# OUT_PIN.net
KiCad netlist of a schematic drawn in Altium Designer
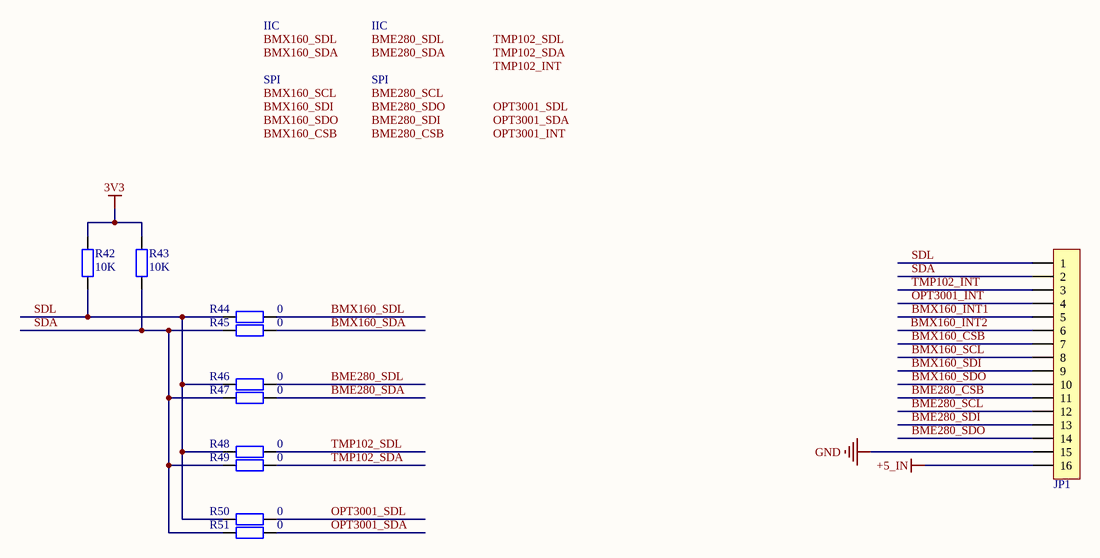
[diagram p0: OUT_PIN.SchDoc]

(export (version "E")
  (design (tool "Eeschema 10.0.6"))
  (components
    (comp (ref "JP1")
      (value "HDR-1X16")
      (footprint "HDR2.54-LI-16P")
      (description "16P接插件")
      (fields (field (name "版权归属") "源创客"))
      (libsource (lib "4.5   - 接插件-脚距2.54") (part "Header 16"))
    )
    (comp (ref "R42")
      (value "10K")
      (footprint "R 0402_L")
      (description "贴片电阻 0402 1%")
      (libsource (lib "3.1   - 电阻-电容-电感") (part "R"))
    )
    (comp (ref "R43")
      (value "10K")
      (footprint "R 0402_L")
      (description "贴片电阻 0402 1%")
      (libsource (lib "3.1   - 电阻-电容-电感") (part "R"))
    )
    (comp (ref "R44")
      (value "0")
      (footprint "R 0402_L")
      (description "贴片电阻")
      (libsource (lib "3.1   - 电阻-电容-电感") (part "R"))
    )
    (comp (ref "R45")
      (value "0")
      (footprint "R 0402_L")
      (description "贴片电阻")
      (libsource (lib "3.1   - 电阻-电容-电感") (part "R"))
    )
    (comp (ref "R46")
      (value "0")
      (footprint "R 0402_L")
      (description "贴片电阻")
      (libsource (lib "3.1   - 电阻-电容-电感") (part "R"))
    )
    (comp (ref "R47")
      (value "0")
      (footprint "R 0402_L")
      (description "贴片电阻")
      (libsource (lib "3.1   - 电阻-电容-电感") (part "R"))
    )
    (comp (ref "R48")
      (value "0")
      (footprint "R 0402_L")
      (description "贴片电阻")
      (libsource (lib "3.1   - 电阻-电容-电感") (part "R"))
    )
    (comp (ref "R49")
      (value "0")
      (footprint "R 0402_L")
      (description "贴片电阻")
      (libsource (lib "3.1   - 电阻-电容-电感") (part "R"))
    )
    (comp (ref "R50")
      (value "0")
      (footprint "R 0402_L")
      (description "贴片电阻")
      (libsource (lib "3.1   - 电阻-电容-电感") (part "R"))
    )
    (comp (ref "R51")
      (value "0")
      (footprint "R 0402_L")
      (description "贴片电阻")
      (libsource (lib "3.1   - 电阻-电容-电感") (part "R"))
    )
  )
  (nets
    (net (code "1") (name "+5_IN") (class "Default")
      (node (ref "JP1") (pin "16") (pinfunction "16_16") (pintype "passive"))
    )
    (net (code "2") (name "/BME280_CSB") (class "Default")
      (node (ref "JP1") (pin "11") (pinfunction "11_11") (pintype "passive"))
    )
    (net (code "3") (name "/BME280_SCL") (class "Default")
      (node (ref "JP1") (pin "12") (pinfunction "12_12") (pintype "passive"))
    )
    (net (code "4") (name "/BME280_SDA") (class "Default")
      (node (ref "R47") (pin "1") (pinfunction "1_1") (pintype "passive"))
    )
    (net (code "5") (name "/BME280_SDI") (class "Default")
      (node (ref "JP1") (pin "13") (pinfunction "13_13") (pintype "passive"))
    )
    (net (code "6") (name "/BME280_SDL") (class "Default")
      (node (ref "R46") (pin "1") (pinfunction "1_1") (pintype "passive"))
    )
    (net (code "7") (name "/BME280_SDO") (class "Default")
      (node (ref "JP1") (pin "14") (pinfunction "14_14") (pintype "passive"))
    )
    (net (code "8") (name "/BMX160_CSB") (class "Default")
      (node (ref "JP1") (pin "7") (pinfunction "7_7") (pintype "passive"))
    )
    (net (code "9") (name "/BMX160_INT1") (class "Default")
      (node (ref "JP1") (pin "5") (pinfunction "5_5") (pintype "passive"))
    )
    (net (code "10") (name "/BMX160_INT2") (class "Default")
      (node (ref "JP1") (pin "6") (pinfunction "6_6") (pintype "passive"))
    )
    (net (code "11") (name "/BMX160_SCL") (class "Default")
      (node (ref "JP1") (pin "8") (pinfunction "8_8") (pintype "passive"))
    )
    (net (code "12") (name "/BMX160_SDA") (class "Default")
      (node (ref "R45") (pin "1") (pinfunction "1_1") (pintype "passive"))
    )
    (net (code "13") (name "/BMX160_SDI") (class "Default")
      (node (ref "JP1") (pin "9") (pinfunction "9_9") (pintype "passive"))
    )
    (net (code "14") (name "/BMX160_SDL") (class "Default")
      (node (ref "R44") (pin "1") (pinfunction "1_1") (pintype "passive"))
    )
    (net (code "15") (name "/BMX160_SDO") (class "Default")
      (node (ref "JP1") (pin "10") (pinfunction "10_10") (pintype "passive"))
    )
    (net (code "16") (name "/OPT3001_INT") (class "Default")
      (node (ref "JP1") (pin "4") (pinfunction "4_4") (pintype "passive"))
    )
    (net (code "17") (name "/OPT3001_SDA") (class "Default")
      (node (ref "R51") (pin "1") (pinfunction "1_1") (pintype "passive"))
    )
    (net (code "18") (name "/OPT3001_SDL") (class "Default")
      (node (ref "R50") (pin "1") (pinfunction "1_1") (pintype "passive"))
    )
    (net (code "19") (name "/SDA") (class "Default")
      (node (ref "JP1") (pin "2") (pinfunction "2_2") (pintype "passive"))
      (node (ref "R43") (pin "2") (pinfunction "2_2") (pintype "passive"))
      (node (ref "R45") (pin "2") (pinfunction "2_2") (pintype "passive"))
      (node (ref "R47") (pin "2") (pinfunction "2_2") (pintype "passive"))
      (node (ref "R49") (pin "2") (pinfunction "2_2") (pintype "passive"))
      (node (ref "R51") (pin "2") (pinfunction "2_2") (pintype "passive"))
    )
    (net (code "20") (name "/SDL") (class "Default")
      (node (ref "JP1") (pin "1") (pinfunction "1_1") (pintype "passive"))
      (node (ref "R42") (pin "2") (pinfunction "2_2") (pintype "passive"))
      (node (ref "R44") (pin "2") (pinfunction "2_2") (pintype "passive"))
      (node (ref "R46") (pin "2") (pinfunction "2_2") (pintype "passive"))
      (node (ref "R48") (pin "2") (pinfunction "2_2") (pintype "passive"))
      (node (ref "R50") (pin "2") (pinfunction "2_2") (pintype "passive"))
    )
    (net (code "21") (name "/TMP102_INT") (class "Default")
      (node (ref "JP1") (pin "3") (pinfunction "3_3") (pintype "passive"))
    )
    (net (code "22") (name "/TMP102_SDA") (class "Default")
      (node (ref "R49") (pin "1") (pinfunction "1_1") (pintype "passive"))
    )
    (net (code "23") (name "/TMP102_SDL") (class "Default")
      (node (ref "R48") (pin "1") (pinfunction "1_1") (pintype "passive"))
    )
    (net (code "24") (name "3V3") (class "Default")
      (node (ref "R42") (pin "1") (pinfunction "1_1") (pintype "passive"))
      (node (ref "R43") (pin "1") (pinfunction "1_1") (pintype "passive"))
    )
    (net (code "25") (name "GND") (class "Default")
      (node (ref "JP1") (pin "15") (pinfunction "15_15") (pintype "passive"))
    )
  )
)
